# STM32.net
KiCad netlist of a schematic drawn in Altium Designer
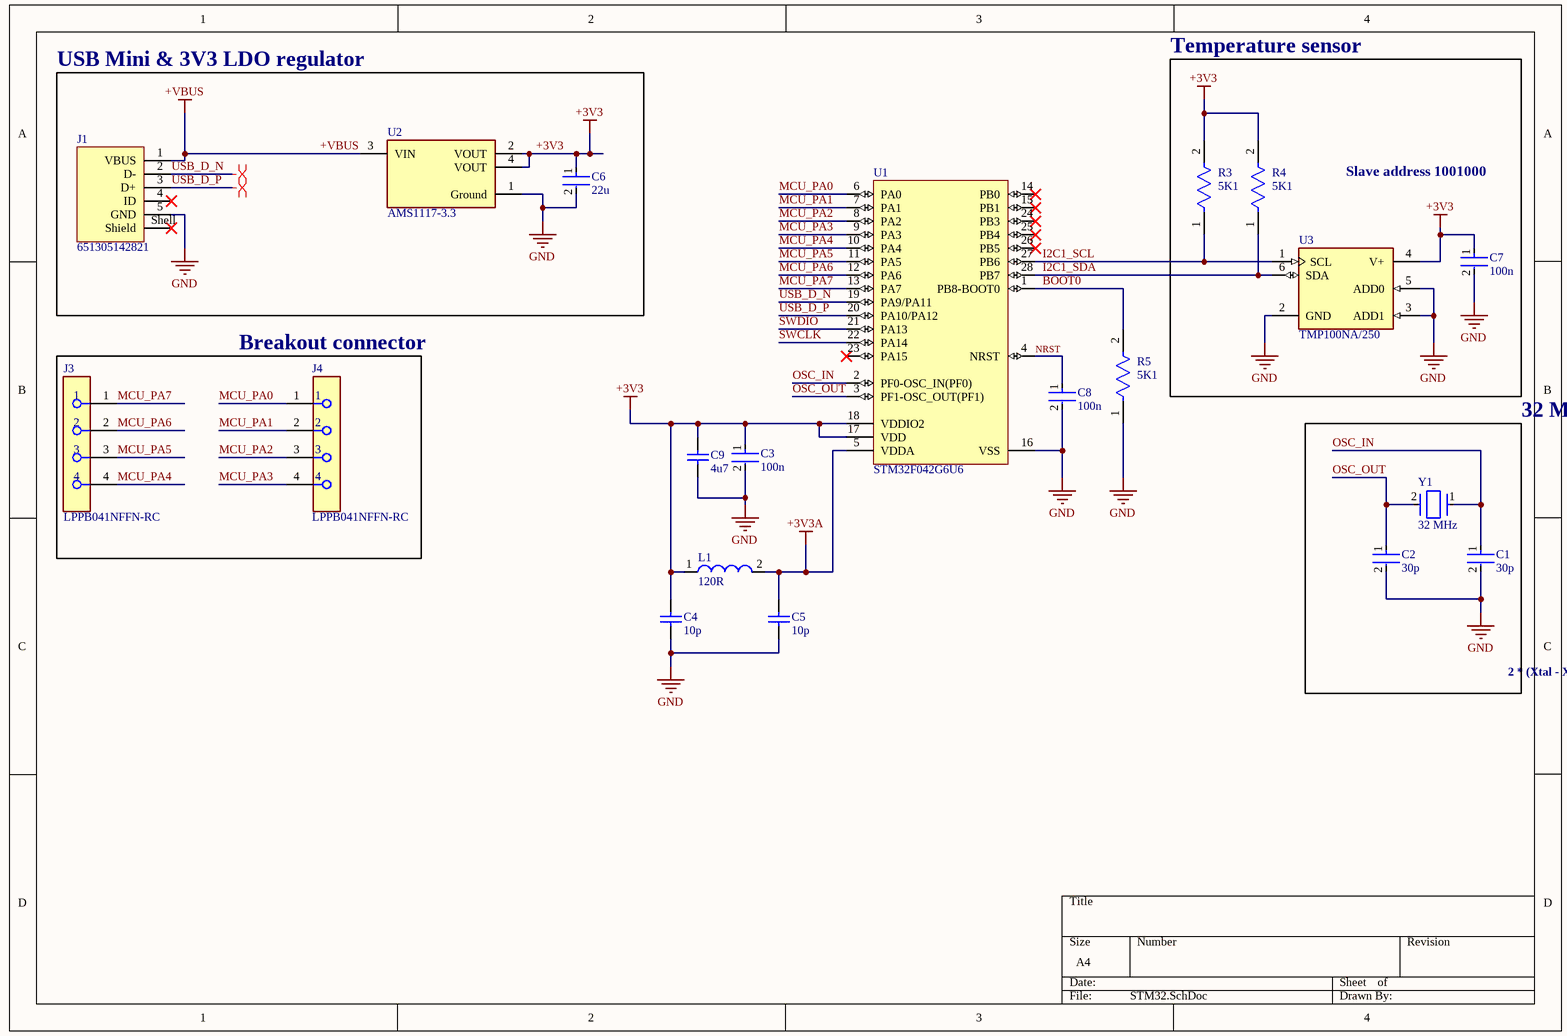
[diagram p0: STM32.SchDoc]

(export (version "E")
  (design (tool "Eeschema 10.0.6"))
  (components
    (comp (ref "C1")
      (value "30p")
      (footprint "FP-C0603C-CF-MFG")
      (description "CAP CER 30PF 50V 5% NP0 0603")
      (fields
        (field (name "MANUFACTURER PART NUMBER") "C0603C300J5GACTU")
        (field (name "MANUFACTURER") "KEMET")
      )
      (libsource (lib "Altium Content Vault") (part "b4654b650e69147ec39a6b967a45e02"))
    )
    (comp (ref "C2")
      (value "30p")
      (footprint "FP-C0603C-CF-MFG")
      (description "CAP CER 30PF 50V 5% NP0 0603")
      (fields
        (field (name "MANUFACTURER PART NUMBER") "C0603C300J5GACTU")
        (field (name "MANUFACTURER") "KEMET")
      )
      (libsource (lib "Altium Content Vault") (part "b4654b650e69147ec39a6b967a45e02"))
    )
    (comp (ref "C3")
      (value "100n")
      (footprint "FP-GRM033-0_03-MFG")
      (description "Chip Multilayer Ceramic Capacitors for General Purpose, 0201, 0.10uF, X5R, 15%, 10%, 6.3V")
      (fields (field (name "VOLTAGE") "6.3V") (field (name "TOLERANCE") "10%"))
      (libsource (lib "Altium Content Vault") (part "b4654b650e69147ec39a6b967a45e02"))
    )
    (comp (ref "C4")
      (value "10p")
      (footprint "CAPC1006X50X20ML10T10")
      (fields
        (field (name "MANUFACTURER") "AVX Interconnect / Elco")
        (field (name "PART NUMBER") "0402YJ100FBSTR")
      )
      (libsource (lib "Altium Content Vault") (part "CAP"))
    )
    (comp (ref "C5")
      (value "10p")
      (footprint "CAPC1006X50X20ML10T10")
      (fields
        (field (name "MANUFACTURER") "AVX Interconnect / Elco")
        (field (name "PART NUMBER") "0402YJ100FBSTR")
      )
      (libsource (lib "Altium Content Vault") (part "CAP"))
    )
    (comp (ref "C6")
      (value "22u")
      (footprint "FP-GRM21B-0_15-MFG")
      (description "Chip Multilayer Ceramic Capacitors for General Purpose, 0805, 22uF, X5R, 15%, 20%, 6.3V")
      (fields (field (name "VOLTAGE") "6.3V") (field (name "TOLERANCE") "20%"))
      (libsource (lib "Altium Content Vault") (part "b4654b650e69147ec39a6b967a45e02"))
    )
    (comp (ref "C7")
      (value "100n")
      (footprint "FP-GRM033-0_03-MFG")
      (description "Chip Multilayer Ceramic Capacitors for General Purpose, 0201, 0.10uF, X5R, 15%, 10%, 6.3V")
      (fields (field (name "VOLTAGE") "6.3V") (field (name "TOLERANCE") "10%"))
      (libsource (lib "Altium Content Vault") (part "b4654b650e69147ec39a6b967a45e02"))
    )
    (comp (ref "C8")
      (value "100n")
      (footprint "FP-GRM033-0_03-MFG")
      (description "Chip Multilayer Ceramic Capacitors for General Purpose, 0201, 0.10uF, X5R, 15%, 10%, 6.3V")
      (fields (field (name "VOLTAGE") "6.3V") (field (name "TOLERANCE") "10%"))
      (libsource (lib "Altium Content Vault") (part "b4654b650e69147ec39a6b967a45e02"))
    )
    (comp (ref "C9")
      (value "4u7")
      (footprint "CAPC1608X87X35NL15T15")
      (fields (field (name "PART NUMBER") "C0603C475K8PACTU") (field (name "MANUFACTURER") "Kemet"))
      (libsource (lib "Altium Content Vault") (part "CAP"))
    )
    (comp (ref "J1")
      (value "651305142821")
      (footprint "651305142821")
      (libsource (lib "Altium Content Vault") (part "Mini USB 2.0_Type AB_Receptacle_1 Port"))
    )
    (comp (ref "J3")
      (value "LPPB041NFFN-RC")
      (footprint "FP-LPPB041NFFN-RC-MFG")
      (description "CONN HDR 4POS 0.05 GOLD PCB")
      (libsource (lib "Altium Content Vault") (part "56792406a6bd5c25e158f553ecd1aa7"))
    )
    (comp (ref "J4")
      (value "LPPB041NFFN-RC")
      (footprint "FP-LPPB041NFFN-RC-MFG")
      (description "CONN HDR 4POS 0.05 GOLD PCB")
      (libsource (lib "") (part "56792406a6bd5c25e158f553ecd1aa7_1"))
    )
    (comp (ref "L1")
      (value "120R")
      (footprint "SMD-1812")
      (description "SMD EMI Suppression Ferrite Bead WE-CBF, Z = 120 Ohm")
      (libsource (lib "Altium Content Vault") (part "PAS-IND-INDUCTOR-2"))
    )
    (comp (ref "R3")
      (value "5K1")
      (footprint "FP-AC0402-MFG")
      (description "RES 5.1kΩ ±1% 0.063W 0402")
      (fields (field (name "TOLERANCE") "1%"))
      (libsource (lib "Altium Content Vault") (part "1029c3af85768c4190bb7ad29bc67b5"))
    )
    (comp (ref "R4")
      (value "5K1")
      (footprint "FP-AC0402-MFG")
      (description "RES 5.1kΩ ±1% 0.063W 0402")
      (fields (field (name "TOLERANCE") "1%"))
      (libsource (lib "Altium Content Vault") (part "1029c3af85768c4190bb7ad29bc67b5"))
    )
    (comp (ref "R5")
      (value "5K1")
      (footprint "FP-AC0402-MFG")
      (description "RES 5.1kΩ ±1% 0.063W 0402")
      (fields (field (name "TOLERANCE") "1%"))
      (libsource (lib "Altium Content Vault") (part "1029c3af85768c4190bb7ad29bc67b5"))
    )
    (comp (ref "U1")
      (value "STM32F042G6U6")
      (footprint "STM-UFQFPN28_V")
      (fields (field (name "MANUFACTURER") "STMicroelectronics"))
      (libsource (lib "Altium Content Vault") (part "MC-ARM-STM32F042-UFQFPN28"))
    )
    (comp (ref "U2")
      (value "AMS1117-3.3")
      (footprint "FP-AMS1117-IPC_C")
      (description "LDO Voltage Regulators 1A, 3.3V")
      (fields
        (field (name "OCTOPART") "https://octopart.com/ams1117-3.3-advanced+monolithic+systems-25899300")
        (field (name "MANUFACTURER") "Advanced Monolithic Systems")
      )
      (libsource (lib "Altium Content Vault") (part "8bdbb5f8e77002000e30dd2845d0354"))
    )
    (comp (ref "U3")
      (value "TMP100NA/250")
      (footprint "FP-DBV0006A-MFG")
      (description "SENSOR DIGITAL -55C-125C SOT23-6")
      (fields
        (field (name "OCTOPART") "https://octopart.com/tmp100na%2F250-texas+instruments-515369")
        (field (name "MANUFACTURER") "Texas Instruments")
      )
      (libsource (lib "Altium Content Vault") (part "7096ef5d9cdcd0587883cd61681e56e"))
    )
    (comp (ref "Y1")
      (value "32 MHz")
      (footprint "FP-ABM7-MFG")
      (description "Crystal 32MHz ±20ppm 18pF SMD-2 6mm x 3.5mm")
      (fields (field (name "TOLERANCE") "20ppm"))
      (libsource (lib "Altium Content Vault") (part "c23a69dc6c9e2f18f2079038eb95dd1"))
    )
  )
  (nets
    (net (code "1") (name "+3V3") (class "Default")
      (node (ref "C3") (pin "1") (pinfunction "1_1") (pintype "passive"))
      (node (ref "C4") (pin "2") (pinfunction "2_2") (pintype "passive"))
      (node (ref "C6") (pin "1") (pinfunction "1_1") (pintype "passive"))
      (node (ref "C7") (pin "1") (pinfunction "1_1") (pintype "passive"))
      (node (ref "C9") (pin "2") (pinfunction "2_2") (pintype "passive"))
      (node (ref "L1") (pin "1") (pinfunction "1_1") (pintype "passive"))
      (node (ref "R3") (pin "2") (pinfunction "2_2") (pintype "passive"))
      (node (ref "R4") (pin "2") (pinfunction "2_2") (pintype "passive"))
      (node (ref "U1") (pin "17") (pinfunction "VDD_17") (pintype "power_in"))
      (node (ref "U1") (pin "18") (pinfunction "VDDIO2_18") (pintype "power_in"))
      (node (ref "U2") (pin "2") (pinfunction "VOUT_2") (pintype "passive"))
      (node (ref "U2") (pin "4") (pinfunction "VOUT_4") (pintype "passive"))
      (node (ref "U3") (pin "4") (pinfunction "V+_4") (pintype "power_in"))
    )
    (net (code "2") (name "+3V3A") (class "Default")
      (node (ref "C5") (pin "2") (pinfunction "2_2") (pintype "passive"))
      (node (ref "L1") (pin "2") (pinfunction "2_2") (pintype "passive"))
      (node (ref "U1") (pin "5") (pinfunction "VDDA_5") (pintype "power_in"))
    )
    (net (code "3") (name "+VBUS") (class "Default")
      (node (ref "J1") (pin "1") (pinfunction "VBUS_1") (pintype "passive"))
      (node (ref "U2") (pin "3") (pinfunction "VIN_3") (pintype "power_in"))
    )
    (net (code "4") (name "/BOOT0") (class "Default")
      (node (ref "R5") (pin "2") (pinfunction "2_2") (pintype "passive"))
      (node (ref "U1") (pin "1") (pinfunction "PB8-BOOT0_1") (pintype "bidirectional"))
    )
    (net (code "5") (name "/I2C1_SCL") (class "Default")
      (node (ref "R3") (pin "1") (pinfunction "1_1") (pintype "passive"))
      (node (ref "U1") (pin "27") (pinfunction "PB6_27") (pintype "bidirectional"))
      (node (ref "U3") (pin "1") (pinfunction "SCL_1") (pintype "input"))
    )
    (net (code "6") (name "/I2C1_SDA") (class "Default")
      (node (ref "R4") (pin "1") (pinfunction "1_1") (pintype "passive"))
      (node (ref "U1") (pin "28") (pinfunction "PB7_28") (pintype "bidirectional"))
      (node (ref "U3") (pin "6") (pinfunction "SDA_6") (pintype "bidirectional"))
    )
    (net (code "7") (name "/MCU_PA0") (class "Default")
      (node (ref "J4") (pin "1") (pinfunction "1_1") (pintype "passive"))
      (node (ref "U1") (pin "6") (pinfunction "PA0_6") (pintype "bidirectional"))
    )
    (net (code "8") (name "/MCU_PA1") (class "Default")
      (node (ref "J4") (pin "2") (pinfunction "2_2") (pintype "passive"))
      (node (ref "U1") (pin "7") (pinfunction "PA1_7") (pintype "bidirectional"))
    )
    (net (code "9") (name "/MCU_PA2") (class "Default")
      (node (ref "J4") (pin "3") (pinfunction "3_3") (pintype "passive"))
      (node (ref "U1") (pin "8") (pinfunction "PA2_8") (pintype "bidirectional"))
    )
    (net (code "10") (name "/MCU_PA3") (class "Default")
      (node (ref "J4") (pin "4") (pinfunction "4_4") (pintype "passive"))
      (node (ref "U1") (pin "9") (pinfunction "PA3_9") (pintype "bidirectional"))
    )
    (net (code "11") (name "/MCU_PA4") (class "Default")
      (node (ref "J3") (pin "4") (pinfunction "4_4") (pintype "passive"))
      (node (ref "U1") (pin "10") (pinfunction "PA4_10") (pintype "bidirectional"))
    )
    (net (code "12") (name "/MCU_PA5") (class "Default")
      (node (ref "J3") (pin "3") (pinfunction "3_3") (pintype "passive"))
      (node (ref "U1") (pin "11") (pinfunction "PA5_11") (pintype "bidirectional"))
    )
    (net (code "13") (name "/MCU_PA6") (class "Default")
      (node (ref "J3") (pin "2") (pinfunction "2_2") (pintype "passive"))
      (node (ref "U1") (pin "12") (pinfunction "PA6_12") (pintype "bidirectional"))
    )
    (net (code "14") (name "/MCU_PA7") (class "Default")
      (node (ref "J3") (pin "1") (pinfunction "1_1") (pintype "passive"))
      (node (ref "U1") (pin "13") (pinfunction "PA7_13") (pintype "bidirectional"))
    )
    (net (code "15") (name "/NRST") (class "Default")
      (node (ref "C8") (pin "1") (pinfunction "1_1") (pintype "passive"))
      (node (ref "U1") (pin "4") (pinfunction "NRST_4") (pintype "bidirectional"))
    )
    (net (code "16") (name "/OSC_IN") (class "Default")
      (node (ref "C1") (pin "1") (pinfunction "1_1") (pintype "passive"))
      (node (ref "U1") (pin "2") (pinfunction "PF0-OSC_IN(PF0)_2") (pintype "bidirectional"))
      (node (ref "Y1") (pin "1") (pinfunction "1_1") (pintype "passive"))
    )
    (net (code "17") (name "/OSC_OUT") (class "Default")
      (node (ref "C2") (pin "1") (pinfunction "1_1") (pintype "passive"))
      (node (ref "U1") (pin "3") (pinfunction "PF1-OSC_OUT(PF1)_3") (pintype "bidirectional"))
      (node (ref "Y1") (pin "2") (pinfunction "2_2") (pintype "passive"))
    )
    (net (code "18") (name "/SWCLK") (class "Default")
      (node (ref "U1") (pin "22") (pinfunction "PA14_22") (pintype "bidirectional"))
    )
    (net (code "19") (name "/SWDIO") (class "Default")
      (node (ref "U1") (pin "21") (pinfunction "PA13_21") (pintype "bidirectional"))
    )
    (net (code "20") (name "/USB_D_N") (class "Default")
      (node (ref "J1") (pin "2") (pinfunction "D-_2") (pintype "passive"))
      (node (ref "U1") (pin "19") (pinfunction "PA9/PA11_19") (pintype "bidirectional"))
    )
    (net (code "21") (name "/USB_D_P") (class "Default")
      (node (ref "J1") (pin "3") (pinfunction "D+_3") (pintype "passive"))
      (node (ref "U1") (pin "20") (pinfunction "PA10/PA12_20") (pintype "bidirectional"))
    )
    (net (code "22") (name "GND") (class "Default")
      (node (ref "C1") (pin "2") (pinfunction "2_2") (pintype "passive"))
      (node (ref "C2") (pin "2") (pinfunction "2_2") (pintype "passive"))
      (node (ref "C3") (pin "2") (pinfunction "2_2") (pintype "passive"))
      (node (ref "C4") (pin "1") (pinfunction "1_1") (pintype "passive"))
      (node (ref "C5") (pin "1") (pinfunction "1_1") (pintype "passive"))
      (node (ref "C6") (pin "2") (pinfunction "2_2") (pintype "passive"))
      (node (ref "C7") (pin "2") (pinfunction "2_2") (pintype "passive"))
      (node (ref "C8") (pin "2") (pinfunction "2_2") (pintype "passive"))
      (node (ref "C9") (pin "1") (pinfunction "1_1") (pintype "passive"))
      (node (ref "J1") (pin "5") (pinfunction "GND_5") (pintype "passive"))
      (node (ref "R5") (pin "1") (pinfunction "1_1") (pintype "passive"))
      (node (ref "U1") (pin "16") (pinfunction "VSS_16") (pintype "power_in"))
      (node (ref "U2") (pin "1") (pinfunction "Ground_1") (pintype "power_in"))
      (node (ref "U3") (pin "2") (pinfunction "GND_2") (pintype "power_in"))
      (node (ref "U3") (pin "3") (pinfunction "ADD1_3") (pintype "input"))
      (node (ref "U3") (pin "5") (pinfunction "ADD0_5") (pintype "input"))
    )
    (net (code "23") (name "unconnected-(J1-ID-Pad4)") (class "Default")
      (node (ref "J1") (pin "4") (pinfunction "ID_4") (pintype "passive+no_connect"))
    )
    (net (code "24") (name "unconnected-(J1-Shield-PadShell)") (class "Default")
      (node (ref "J1") (pin "Shell") (pinfunction "Shield_Shell") (pintype "passive+no_connect"))
    )
    (net (code "25") (name "unconnected-(U1-PA15-Pad23)") (class "Default")
      (node (ref "U1") (pin "23") (pinfunction "PA15_23") (pintype "bidirectional+no_connect"))
    )
    (net (code "26") (name "unconnected-(U1-PB0-Pad14)") (class "Default")
      (node (ref "U1") (pin "14") (pinfunction "PB0_14") (pintype "bidirectional+no_connect"))
    )
    (net (code "27") (name "unconnected-(U1-PB1-Pad15)") (class "Default")
      (node (ref "U1") (pin "15") (pinfunction "PB1_15") (pintype "bidirectional+no_connect"))
    )
    (net (code "28") (name "unconnected-(U1-PB3-Pad24)") (class "Default")
      (node (ref "U1") (pin "24") (pinfunction "PB3_24") (pintype "bidirectional+no_connect"))
    )
    (net (code "29") (name "unconnected-(U1-PB4-Pad25)") (class "Default")
      (node (ref "U1") (pin "25") (pinfunction "PB4_25") (pintype "bidirectional+no_connect"))
    )
    (net (code "30") (name "unconnected-(U1-PB5-Pad26)") (class "Default")
      (node (ref "U1") (pin "26") (pinfunction "PB5_26") (pintype "bidirectional+no_connect"))
    )
  )
)
